# nrf51822_board.net
KiCad netlist of a schematic drawn in EAGLE
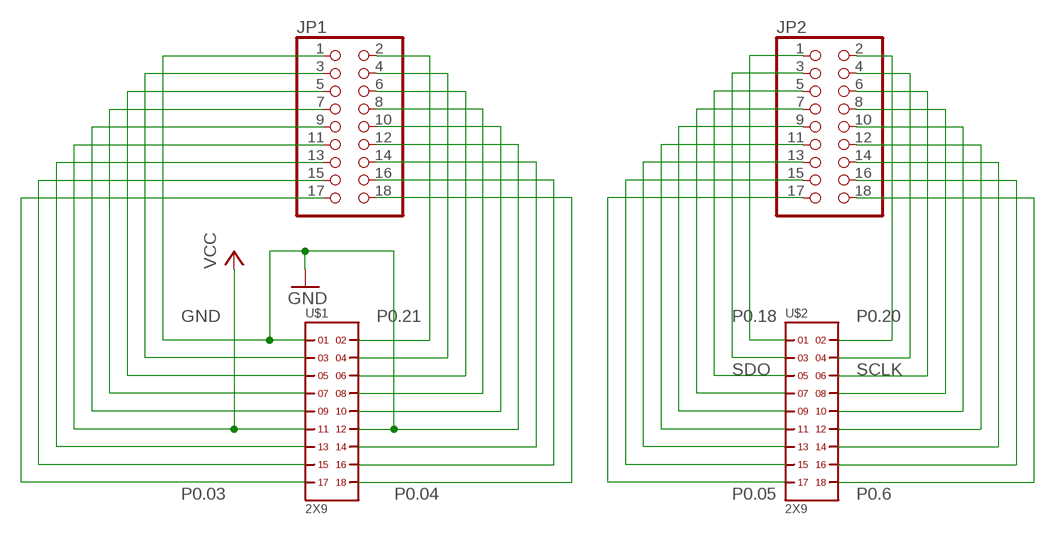
[diagram p0: schematic, sheet 1]

(export (version "E")
  (design (tool "Eeschema 10.0.6"))
  (components
    (comp (ref "JP1")
      (value "PINHD-2X9")
      (footprint "eagle-import:2X09")
      (libsource (lib "eagle-import") (part "PINHD-2X9"))
    )
    (comp (ref "JP2")
      (value "PINHD-2X9")
      (footprint "eagle-import:2X09")
      (libsource (lib "eagle-import") (part "PINHD-2X9"))
    )
    (comp (ref "U$1")
      (value "2X9")
      (footprint "eagle-import:2X9")
      (libsource (lib "eagle-import") (part "2X9"))
    )
    (comp (ref "U$2")
      (value "2X9")
      (footprint "eagle-import:2X9")
      (libsource (lib "eagle-import") (part "2X9"))
    )
  )
  (nets
    (net (code "1") (name "/P0.03") (class "Default")
      (node (ref "JP1") (pin "17") (pinfunction "17_17") (pintype "passive"))
      (node (ref "U$1") (pin "17") (pinfunction "17_17") (pintype "bidirectional"))
    )
    (net (code "2") (name "/P0.04") (class "Default")
      (node (ref "JP1") (pin "18") (pinfunction "18_18") (pintype "passive"))
      (node (ref "U$1") (pin "18") (pinfunction "18_18") (pintype "bidirectional"))
    )
    (net (code "3") (name "/P0.05") (class "Default")
      (node (ref "JP2") (pin "17") (pinfunction "17_17") (pintype "passive"))
      (node (ref "U$2") (pin "17") (pinfunction "17_17") (pintype "bidirectional"))
    )
    (net (code "4") (name "/P0.6") (class "Default")
      (node (ref "JP2") (pin "18") (pinfunction "18_18") (pintype "passive"))
      (node (ref "U$2") (pin "18") (pinfunction "18_18") (pintype "bidirectional"))
    )
    (net (code "5") (name "/P0.18") (class "Default")
      (node (ref "JP2") (pin "1") (pinfunction "1_1") (pintype "passive"))
      (node (ref "U$2") (pin "1") (pinfunction "1_1") (pintype "bidirectional"))
    )
    (net (code "6") (name "/P0.20") (class "Default")
      (node (ref "JP2") (pin "2") (pinfunction "2_2") (pintype "passive"))
      (node (ref "U$2") (pin "2") (pinfunction "2_2") (pintype "bidirectional"))
    )
    (net (code "7") (name "/P0.21") (class "Default")
      (node (ref "JP1") (pin "2") (pinfunction "2_2") (pintype "passive"))
      (node (ref "U$1") (pin "2") (pinfunction "2_2") (pintype "bidirectional"))
    )
    (net (code "8") (name "/SCLK") (class "Default")
      (node (ref "JP2") (pin "6") (pinfunction "6_6") (pintype "passive"))
      (node (ref "U$2") (pin "6") (pinfunction "6_6") (pintype "bidirectional"))
    )
    (net (code "9") (name "/SDO") (class "Default")
      (node (ref "JP2") (pin "5") (pinfunction "5_5") (pintype "passive"))
      (node (ref "U$2") (pin "5") (pinfunction "5_5") (pintype "bidirectional"))
    )
    (net (code "10") (name "GND") (class "Default")
      (node (ref "JP1") (pin "1") (pinfunction "1_1") (pintype "passive"))
      (node (ref "JP1") (pin "12") (pinfunction "12_12") (pintype "passive"))
      (node (ref "U$1") (pin "1") (pinfunction "1_1") (pintype "bidirectional"))
      (node (ref "U$1") (pin "12") (pinfunction "12_12") (pintype "bidirectional"))
    )
    (net (code "11") (name "Net-(JP1-Pad3)") (class "Default")
      (node (ref "JP1") (pin "3") (pinfunction "3_3") (pintype "passive"))
      (node (ref "U$1") (pin "3") (pinfunction "3_3") (pintype "bidirectional"))
    )
    (net (code "12") (name "Net-(JP1-Pad4)") (class "Default")
      (node (ref "JP1") (pin "4") (pinfunction "4_4") (pintype "passive"))
      (node (ref "U$1") (pin "4") (pinfunction "4_4") (pintype "bidirectional"))
    )
    (net (code "13") (name "Net-(JP1-Pad5)") (class "Default")
      (node (ref "JP1") (pin "5") (pinfunction "5_5") (pintype "passive"))
      (node (ref "U$1") (pin "5") (pinfunction "5_5") (pintype "bidirectional"))
    )
    (net (code "14") (name "Net-(JP1-Pad6)") (class "Default")
      (node (ref "JP1") (pin "6") (pinfunction "6_6") (pintype "passive"))
      (node (ref "U$1") (pin "6") (pinfunction "6_6") (pintype "bidirectional"))
    )
    (net (code "15") (name "Net-(JP1-Pad7)") (class "Default")
      (node (ref "JP1") (pin "7") (pinfunction "7_7") (pintype "passive"))
      (node (ref "U$1") (pin "7") (pinfunction "7_7") (pintype "bidirectional"))
    )
    (net (code "16") (name "Net-(JP1-Pad8)") (class "Default")
      (node (ref "JP1") (pin "8") (pinfunction "8_8") (pintype "passive"))
      (node (ref "U$1") (pin "8") (pinfunction "8_8") (pintype "bidirectional"))
    )
    (net (code "17") (name "Net-(JP1-Pad9)") (class "Default")
      (node (ref "JP1") (pin "9") (pinfunction "9_9") (pintype "passive"))
      (node (ref "U$1") (pin "9") (pinfunction "9_9") (pintype "bidirectional"))
    )
    (net (code "18") (name "Net-(JP1-Pad10)") (class "Default")
      (node (ref "JP1") (pin "10") (pinfunction "10_10") (pintype "passive"))
      (node (ref "U$1") (pin "10") (pinfunction "10_10") (pintype "bidirectional"))
    )
    (net (code "19") (name "Net-(JP1-Pad13)") (class "Default")
      (node (ref "JP1") (pin "13") (pinfunction "13_13") (pintype "passive"))
      (node (ref "U$1") (pin "13") (pinfunction "13_13") (pintype "bidirectional"))
    )
    (net (code "20") (name "Net-(JP1-Pad14)") (class "Default")
      (node (ref "JP1") (pin "14") (pinfunction "14_14") (pintype "passive"))
      (node (ref "U$1") (pin "14") (pinfunction "14_14") (pintype "bidirectional"))
    )
    (net (code "21") (name "Net-(JP1-Pad15)") (class "Default")
      (node (ref "JP1") (pin "15") (pinfunction "15_15") (pintype "passive"))
      (node (ref "U$1") (pin "15") (pinfunction "15_15") (pintype "bidirectional"))
    )
    (net (code "22") (name "Net-(JP1-Pad16)") (class "Default")
      (node (ref "JP1") (pin "16") (pinfunction "16_16") (pintype "passive"))
      (node (ref "U$1") (pin "16") (pinfunction "16_16") (pintype "bidirectional"))
    )
    (net (code "23") (name "Net-(JP2-Pad3)") (class "Default")
      (node (ref "JP2") (pin "3") (pinfunction "3_3") (pintype "passive"))
      (node (ref "U$2") (pin "3") (pinfunction "3_3") (pintype "bidirectional"))
    )
    (net (code "24") (name "Net-(JP2-Pad4)") (class "Default")
      (node (ref "JP2") (pin "4") (pinfunction "4_4") (pintype "passive"))
      (node (ref "U$2") (pin "4") (pinfunction "4_4") (pintype "bidirectional"))
    )
    (net (code "25") (name "Net-(JP2-Pad7)") (class "Default")
      (node (ref "JP2") (pin "7") (pinfunction "7_7") (pintype "passive"))
      (node (ref "U$2") (pin "7") (pinfunction "7_7") (pintype "bidirectional"))
    )
    (net (code "26") (name "Net-(JP2-Pad8)") (class "Default")
      (node (ref "JP2") (pin "8") (pinfunction "8_8") (pintype "passive"))
      (node (ref "U$2") (pin "8") (pinfunction "8_8") (pintype "bidirectional"))
    )
    (net (code "27") (name "Net-(JP2-Pad9)") (class "Default")
      (node (ref "JP2") (pin "9") (pinfunction "9_9") (pintype "passive"))
      (node (ref "U$2") (pin "9") (pinfunction "9_9") (pintype "bidirectional"))
    )
    (net (code "28") (name "Net-(JP2-Pad10)") (class "Default")
      (node (ref "JP2") (pin "10") (pinfunction "10_10") (pintype "passive"))
      (node (ref "U$2") (pin "10") (pinfunction "10_10") (pintype "bidirectional"))
    )
    (net (code "29") (name "Net-(JP2-Pad11)") (class "Default")
      (node (ref "JP2") (pin "11") (pinfunction "11_11") (pintype "passive"))
      (node (ref "U$2") (pin "11") (pinfunction "11_11") (pintype "bidirectional"))
    )
    (net (code "30") (name "Net-(JP2-Pad12)") (class "Default")
      (node (ref "JP2") (pin "12") (pinfunction "12_12") (pintype "passive"))
      (node (ref "U$2") (pin "12") (pinfunction "12_12") (pintype "bidirectional"))
    )
    (net (code "31") (name "Net-(JP2-Pad13)") (class "Default")
      (node (ref "JP2") (pin "13") (pinfunction "13_13") (pintype "passive"))
      (node (ref "U$2") (pin "13") (pinfunction "13_13") (pintype "bidirectional"))
    )
    (net (code "32") (name "Net-(JP2-Pad14)") (class "Default")
      (node (ref "JP2") (pin "14") (pinfunction "14_14") (pintype "passive"))
      (node (ref "U$2") (pin "14") (pinfunction "14_14") (pintype "bidirectional"))
    )
    (net (code "33") (name "Net-(JP2-Pad15)") (class "Default")
      (node (ref "JP2") (pin "15") (pinfunction "15_15") (pintype "passive"))
      (node (ref "U$2") (pin "15") (pinfunction "15_15") (pintype "bidirectional"))
    )
    (net (code "34") (name "Net-(JP2-Pad16)") (class "Default")
      (node (ref "JP2") (pin "16") (pinfunction "16_16") (pintype "passive"))
      (node (ref "U$2") (pin "16") (pinfunction "16_16") (pintype "bidirectional"))
    )
    (net (code "35") (name "VCC") (class "Default")
      (node (ref "JP1") (pin "11") (pinfunction "11_11") (pintype "passive"))
      (node (ref "U$1") (pin "11") (pinfunction "11_11") (pintype "bidirectional"))
    )
  )
)
